# jevois_pi.net
KiCad netlist of a schematic drawn in EAGLE
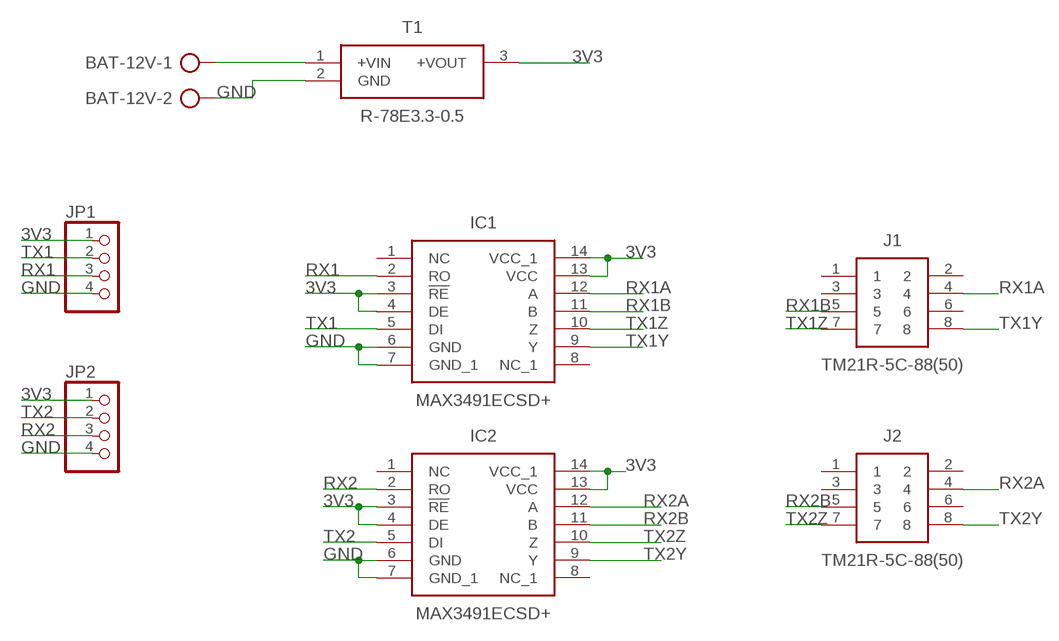
[diagram p0: schematic, sheet 1]

(export (version "E")
  (design (tool "Eeschema 10.0.6"))
  (components
    (comp (ref "BAT-12V")
      (value "AK500/2-H")
      (footprint "eagle-import:AK500_2-H")
      (libsource (lib "eagle-import") (part "AK500/2-H"))
    )
    (comp (ref "IC1")
      (value "MAX3491ECSD+")
      (footprint "eagle-import:SOIC127P600X175-14N")
      (fields (field (name "RS_PART_NUMBER") "7329496"))
      (libsource (lib "eagle-import") (part "MAX3491ECSD+"))
    )
    (comp (ref "IC2")
      (value "MAX3491ECSD+")
      (footprint "eagle-import:SOIC127P600X175-14N")
      (fields (field (name "RS_PART_NUMBER") "7329496"))
      (libsource (lib "eagle-import") (part "MAX3491ECSD+"))
    )
    (comp (ref "J1")
      (value "TM21R-5C-88(50)")
      (footprint "eagle-import:TM21R-5C-88(50)")
      (fields (field (name "RS_PART_NUMBER") "6256710"))
      (libsource (lib "eagle-import") (part "TM21R-5C-88(50)"))
    )
    (comp (ref "J2")
      (value "TM21R-5C-88(50)")
      (footprint "eagle-import:TM21R-5C-88(50)")
      (fields (field (name "RS_PART_NUMBER") "6256710"))
      (libsource (lib "eagle-import") (part "TM21R-5C-88(50)"))
    )
    (comp (ref "JP1")
      (value "PINHD-1X4")
      (footprint "eagle-import:1X04")
      (libsource (lib "eagle-import") (part "PINHD-1X4"))
    )
    (comp (ref "JP2")
      (value "PINHD-1X4")
      (footprint "eagle-import:1X04")
      (libsource (lib "eagle-import") (part "PINHD-1X4"))
    )
    (comp (ref "T1")
      (value "R-78E3.3-0.5")
      (footprint "eagle-import:SHDRV3W100P0_254_1X3_1160X850X")
      (fields (field (name "RS_PART_NUMBER") "7773291"))
      (libsource (lib "eagle-import") (part "R-78E3.3-0.5"))
    )
  )
  (nets
    (net (code "1") (name "/3V3") (class "Default")
      (node (ref "IC1") (pin "13") (pinfunction "VCC_13") (pintype "power_in"))
      (node (ref "IC1") (pin "14") (pinfunction "VCC_1_14") (pintype "power_in"))
      (node (ref "IC1") (pin "3") (pinfunction "~{RE}_3") (pintype "input"))
      (node (ref "IC1") (pin "4") (pinfunction "DE_4") (pintype "input"))
      (node (ref "IC2") (pin "13") (pinfunction "VCC_13") (pintype "power_in"))
      (node (ref "IC2") (pin "14") (pinfunction "VCC_1_14") (pintype "power_in"))
      (node (ref "IC2") (pin "3") (pinfunction "~{RE}_3") (pintype "input"))
      (node (ref "IC2") (pin "4") (pinfunction "DE_4") (pintype "input"))
      (node (ref "JP1") (pin "1") (pinfunction "1_1") (pintype "passive"))
      (node (ref "JP2") (pin "1") (pinfunction "1_1") (pintype "passive"))
      (node (ref "T1") (pin "3") (pinfunction "+VOUT_3") (pintype "output"))
    )
    (net (code "2") (name "/GND") (class "Default")
      (node (ref "BAT-12V") (pin "2") (pinfunction "KL_2") (pintype "passive"))
      (node (ref "IC1") (pin "6") (pinfunction "GND_6") (pintype "power_in"))
      (node (ref "IC1") (pin "7") (pinfunction "GND_1_7") (pintype "power_in"))
      (node (ref "IC2") (pin "6") (pinfunction "GND_6") (pintype "power_in"))
      (node (ref "IC2") (pin "7") (pinfunction "GND_1_7") (pintype "power_in"))
      (node (ref "JP1") (pin "4") (pinfunction "4_4") (pintype "passive"))
      (node (ref "JP2") (pin "4") (pinfunction "4_4") (pintype "passive"))
      (node (ref "T1") (pin "2") (pinfunction "GND_2") (pintype "power_in"))
    )
    (net (code "3") (name "/RX1") (class "Default")
      (node (ref "IC1") (pin "2") (pinfunction "RO_2") (pintype "output"))
      (node (ref "JP1") (pin "3") (pinfunction "3_3") (pintype "passive"))
    )
    (net (code "4") (name "/RX1A") (class "Default")
      (node (ref "IC1") (pin "12") (pinfunction "A_12") (pintype "input"))
      (node (ref "J1") (pin "4") (pinfunction "4_4") (pintype "passive"))
    )
    (net (code "5") (name "/RX1B") (class "Default")
      (node (ref "IC1") (pin "11") (pinfunction "B_11") (pintype "input"))
      (node (ref "J1") (pin "5") (pinfunction "5_5") (pintype "passive"))
    )
    (net (code "6") (name "/RX2") (class "Default")
      (node (ref "IC2") (pin "2") (pinfunction "RO_2") (pintype "output"))
      (node (ref "JP2") (pin "3") (pinfunction "3_3") (pintype "passive"))
    )
    (net (code "7") (name "/RX2A") (class "Default")
      (node (ref "IC2") (pin "12") (pinfunction "A_12") (pintype "input"))
      (node (ref "J2") (pin "4") (pinfunction "4_4") (pintype "passive"))
    )
    (net (code "8") (name "/RX2B") (class "Default")
      (node (ref "IC2") (pin "11") (pinfunction "B_11") (pintype "input"))
      (node (ref "J2") (pin "5") (pinfunction "5_5") (pintype "passive"))
    )
    (net (code "9") (name "/TX1") (class "Default")
      (node (ref "IC1") (pin "5") (pinfunction "DI_5") (pintype "input"))
      (node (ref "JP1") (pin "2") (pinfunction "2_2") (pintype "passive"))
    )
    (net (code "10") (name "/TX1Y") (class "Default")
      (node (ref "IC1") (pin "9") (pinfunction "Y_9") (pintype "output"))
      (node (ref "J1") (pin "8") (pinfunction "8_8") (pintype "passive"))
    )
    (net (code "11") (name "/TX1Z") (class "Default")
      (node (ref "IC1") (pin "10") (pinfunction "Z_10") (pintype "output"))
      (node (ref "J1") (pin "7") (pinfunction "7_7") (pintype "passive"))
    )
    (net (code "12") (name "/TX2") (class "Default")
      (node (ref "IC2") (pin "5") (pinfunction "DI_5") (pintype "input"))
      (node (ref "JP2") (pin "2") (pinfunction "2_2") (pintype "passive"))
    )
    (net (code "13") (name "/TX2Y") (class "Default")
      (node (ref "IC2") (pin "9") (pinfunction "Y_9") (pintype "output"))
      (node (ref "J2") (pin "8") (pinfunction "8_8") (pintype "passive"))
    )
    (net (code "14") (name "/TX2Z") (class "Default")
      (node (ref "IC2") (pin "10") (pinfunction "Z_10") (pintype "output"))
      (node (ref "J2") (pin "7") (pinfunction "7_7") (pintype "passive"))
    )
    (net (code "15") (name "Net-(BAT-12VA-KL)") (class "Default")
      (node (ref "BAT-12V") (pin "1") (pinfunction "KL_1") (pintype "passive"))
      (node (ref "T1") (pin "1") (pinfunction "+VIN_1") (pintype "input"))
    )
    (net (code "16") (name "unconnected-(IC1-NC-Pad1)") (class "Default")
      (node (ref "IC1") (pin "1") (pinfunction "NC_1") (pintype "no_connect"))
    )
    (net (code "17") (name "unconnected-(IC1-NC_1-Pad8)") (class "Default")
      (node (ref "IC1") (pin "8") (pinfunction "NC_1_8") (pintype "passive"))
    )
    (net (code "18") (name "unconnected-(IC2-NC-Pad1)") (class "Default")
      (node (ref "IC2") (pin "1") (pinfunction "NC_1") (pintype "no_connect"))
    )
    (net (code "19") (name "unconnected-(IC2-NC_1-Pad8)") (class "Default")
      (node (ref "IC2") (pin "8") (pinfunction "NC_1_8") (pintype "passive"))
    )
    (net (code "20") (name "unconnected-(J1-Pad1)") (class "Default")
      (node (ref "J1") (pin "1") (pinfunction "1_1") (pintype "passive"))
    )
    (net (code "21") (name "unconnected-(J1-Pad2)") (class "Default")
      (node (ref "J1") (pin "2") (pinfunction "2_2") (pintype "passive"))
    )
    (net (code "22") (name "unconnected-(J1-Pad3)") (class "Default")
      (node (ref "J1") (pin "3") (pinfunction "3_3") (pintype "passive"))
    )
    (net (code "23") (name "unconnected-(J1-Pad6)") (class "Default")
      (node (ref "J1") (pin "6") (pinfunction "6_6") (pintype "passive"))
    )
    (net (code "24") (name "unconnected-(J2-Pad1)") (class "Default")
      (node (ref "J2") (pin "1") (pinfunction "1_1") (pintype "passive"))
    )
    (net (code "25") (name "unconnected-(J2-Pad2)") (class "Default")
      (node (ref "J2") (pin "2") (pinfunction "2_2") (pintype "passive"))
    )
    (net (code "26") (name "unconnected-(J2-Pad3)") (class "Default")
      (node (ref "J2") (pin "3") (pinfunction "3_3") (pintype "passive"))
    )
    (net (code "27") (name "unconnected-(J2-Pad6)") (class "Default")
      (node (ref "J2") (pin "6") (pinfunction "6_6") (pintype "passive"))
    )
  )
)
